# STM8.net
KiCad netlist of a schematic drawn in Altium Designer
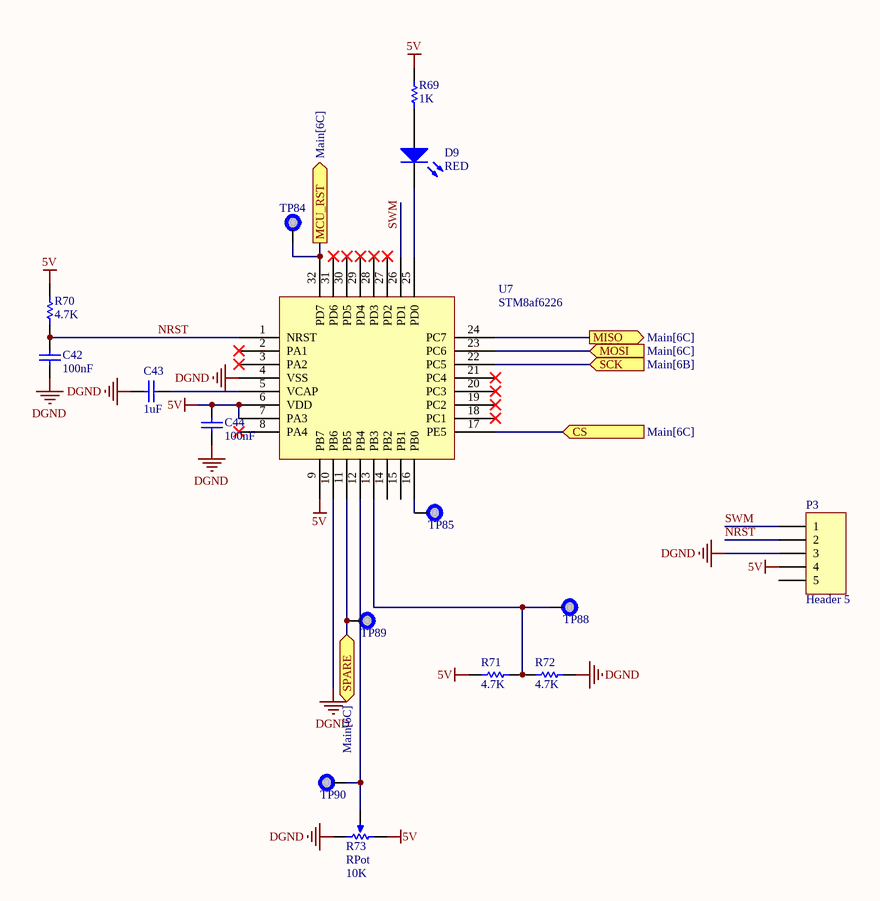
[diagram p0: STM8.SchDoc]

(export (version "E")
  (design (tool "Eeschema 10.0.6"))
  (components
    (comp (ref "C42")
      (value "100nF")
      (footprint "0603c")
      (description "LOW ESR")
      (fields (field (name "PUBLISHER") "Altium Limited"))
      (libsource (lib "Miscellaneous Devices") (part "Cap"))
    )
    (comp (ref "C43")
      (value "1uF")
      (footprint "0805c")
      (description "LOW ESR")
      (fields (field (name "PUBLISHER") "Altium Limited"))
      (libsource (lib "Miscellaneous Devices") (part "Cap"))
    )
    (comp (ref "C44")
      (value "100nF")
      (footprint "0603c")
      (description "LOW ESR")
      (fields (field (name "PUBLISHER") "Altium Limited"))
      (libsource (lib "Miscellaneous Devices") (part "Cap"))
    )
    (comp (ref "D9")
      (value "RED")
      (footprint "0805LED")
      (fields (field (name "PUBLISHER") "Altium Limited"))
      (libsource (lib "Miscellaneous Devices") (part "LED0"))
    )
    (comp (ref "P3")
      (value "Header 5")
      (footprint "HDR1X5")
      (description "Header, 5-Pin")
      (fields (field (name "PUBLISHER") "Altium Limited"))
      (libsource (lib "Miscellaneous Connectors") (part "Header 5"))
    )
    (comp (ref "R69")
      (value "1K")
      (footprint "0805")
      (description "Resistor")
      (fields (field (name "PUBLISHER") "Altium Limited"))
      (libsource (lib "Miscellaneous Devices") (part "Res1"))
    )
    (comp (ref "R70")
      (value "4.7K")
      (footprint "0805")
      (description "Resistor")
      (fields (field (name "PUBLISHER") "Altium Limited"))
      (libsource (lib "Miscellaneous Devices") (part "Res1"))
    )
    (comp (ref "R71")
      (value "4.7K")
      (footprint "0805")
      (description "Resistor")
      (fields (field (name "PUBLISHER") "Altium Limited"))
      (libsource (lib "Miscellaneous Devices") (part "Res1"))
    )
    (comp (ref "R72")
      (value "4.7K")
      (footprint "0805")
      (description "Resistor")
      (fields (field (name "PUBLISHER") "Altium Limited"))
      (libsource (lib "Miscellaneous Devices") (part "Res1"))
    )
    (comp (ref "R73")
      (value "RPot")
      (footprint "POT-MULTITURN")
      (description "MultiTurn")
      (fields (field (name "ALTIUM_VALUE") "10K") (field (name "PUBLISHER") "Altium Limited"))
      (libsource (lib "Miscellaneous Devices") (part "RPot"))
    )
    (comp (ref "TP84") (value "TestPoint") (footprint "TP") (libsource (lib "SchlibV0.1") (part "TestPoint")))
    (comp (ref "TP85") (value "TestPoint") (footprint "TP") (libsource (lib "SchlibV0.1") (part "TestPoint")))
    (comp (ref "TP88") (value "TestPoint") (footprint "TP") (libsource (lib "SchlibV0.1") (part "TestPoint")))
    (comp (ref "TP89") (value "TestPoint") (footprint "TP") (libsource (lib "SchlibV0.1") (part "TestPoint")))
    (comp (ref "TP90") (value "TestPoint") (footprint "TP") (libsource (lib "SchlibV0.1") (part "TestPoint")))
    (comp (ref "U7")
      (value "STM8af6226")
      (footprint "LQFP-32")
      (libsource (lib "SchlibV0.1") (part "STM8af6226"))
    )
  )
  (nets
    (net (code "1") (name "/CS") (class "Default")
      (node (ref "U7") (pin "17") (pinfunction "PE5_17") (pintype "passive"))
    )
    (net (code "2") (name "/MCU_RST") (class "Default")
      (node (ref "TP84") (pin "1") (pintype "passive"))
      (node (ref "U7") (pin "32") (pinfunction "PD7_32") (pintype "passive"))
    )
    (net (code "3") (name "/MISO") (class "Default")
      (node (ref "U7") (pin "24") (pinfunction "PC7_24") (pintype "passive"))
    )
    (net (code "4") (name "/MOSI") (class "Default")
      (node (ref "U7") (pin "23") (pinfunction "PC6_23") (pintype "passive"))
    )
    (net (code "5") (name "/NRST") (class "Default")
      (node (ref "C42") (pin "1") (pinfunction "1_1") (pintype "passive"))
      (node (ref "P3") (pin "2") (pinfunction "2_2") (pintype "passive"))
      (node (ref "R70") (pin "2") (pinfunction "2_2") (pintype "passive"))
      (node (ref "U7") (pin "1") (pinfunction "NRST_1") (pintype "passive"))
    )
    (net (code "6") (name "/SCK") (class "Default")
      (node (ref "U7") (pin "22") (pinfunction "PC5_22") (pintype "passive"))
    )
    (net (code "7") (name "/SPARE") (class "Default")
      (node (ref "TP89") (pin "1") (pintype "passive"))
      (node (ref "U7") (pin "11") (pinfunction "PB5_11") (pintype "passive"))
    )
    (net (code "8") (name "/SWM") (class "Default")
      (node (ref "P3") (pin "1") (pinfunction "1_1") (pintype "passive"))
      (node (ref "U7") (pin "26") (pinfunction "PD1_26") (pintype "passive"))
    )
    (net (code "9") (name "5V") (class "Default")
      (node (ref "C44") (pin "1") (pinfunction "1_1") (pintype "passive"))
      (node (ref "P3") (pin "4") (pinfunction "4_4") (pintype "passive"))
      (node (ref "R69") (pin "2") (pinfunction "2_2") (pintype "passive"))
      (node (ref "R70") (pin "1") (pinfunction "1_1") (pintype "passive"))
      (node (ref "R71") (pin "2") (pinfunction "2_2") (pintype "passive"))
      (node (ref "R73") (pin "1") (pinfunction "TOP_1") (pintype "passive"))
      (node (ref "U7") (pin "6") (pinfunction "VDD_6") (pintype "passive"))
      (node (ref "U7") (pin "7") (pinfunction "PA3_7") (pintype "passive"))
      (node (ref "U7") (pin "9") (pinfunction "PB7_9") (pintype "passive"))
    )
    (net (code "10") (name "DGND") (class "Default")
      (node (ref "C42") (pin "2") (pinfunction "2_2") (pintype "passive"))
      (node (ref "C43") (pin "2") (pinfunction "2_2") (pintype "passive"))
      (node (ref "C44") (pin "2") (pinfunction "2_2") (pintype "passive"))
      (node (ref "P3") (pin "3") (pinfunction "3_3") (pintype "passive"))
      (node (ref "R72") (pin "1") (pinfunction "1_1") (pintype "passive"))
      (node (ref "R73") (pin "3") (pinfunction "BOT_3") (pintype "passive"))
      (node (ref "U7") (pin "10") (pinfunction "PB6_10") (pintype "passive"))
      (node (ref "U7") (pin "4") (pinfunction "VSS_4") (pintype "passive"))
    )
    (net (code "11") (name "Net-(D9-A)") (class "Default")
      (node (ref "D9") (pin "1") (pinfunction "A_1") (pintype "passive"))
      (node (ref "R69") (pin "1") (pinfunction "1_1") (pintype "passive"))
    )
    (net (code "12") (name "Net-(D9-K)") (class "Default")
      (node (ref "D9") (pin "2") (pinfunction "K_2") (pintype "passive"))
      (node (ref "U7") (pin "25") (pinfunction "PD0_25") (pintype "passive"))
    )
    (net (code "13") (name "Net-(R73-TAP)") (class "Default")
      (node (ref "R73") (pin "2") (pinfunction "TAP_2") (pintype "passive"))
      (node (ref "TP90") (pin "1") (pintype "passive"))
      (node (ref "U7") (pin "12") (pinfunction "PB4_12") (pintype "passive"))
    )
    (net (code "14") (name "Net-(U7-PB0)") (class "Default")
      (node (ref "TP85") (pin "1") (pintype "passive"))
      (node (ref "U7") (pin "16") (pinfunction "PB0_16") (pintype "passive"))
    )
    (net (code "15") (name "Net-(U7-PB3)") (class "Default")
      (node (ref "R71") (pin "1") (pinfunction "1_1") (pintype "passive"))
      (node (ref "R72") (pin "2") (pinfunction "2_2") (pintype "passive"))
      (node (ref "TP88") (pin "1") (pintype "passive"))
      (node (ref "U7") (pin "13") (pinfunction "PB3_13") (pintype "passive"))
    )
    (net (code "16") (name "Net-(U7-VCAP)") (class "Default")
      (node (ref "C43") (pin "1") (pinfunction "1_1") (pintype "passive"))
      (node (ref "U7") (pin "5") (pinfunction "VCAP_5") (pintype "passive"))
    )
    (net (code "17") (name "unconnected-(P3-Pad5)") (class "Default")
      (node (ref "P3") (pin "5") (pinfunction "5_5") (pintype "passive"))
    )
    (net (code "18") (name "unconnected-(U7-PA1-Pad2)") (class "Default")
      (node (ref "U7") (pin "2") (pinfunction "PA1_2") (pintype "passive+no_connect"))
    )
    (net (code "19") (name "unconnected-(U7-PA2-Pad3)") (class "Default")
      (node (ref "U7") (pin "3") (pinfunction "PA2_3") (pintype "passive+no_connect"))
    )
    (net (code "20") (name "unconnected-(U7-PA4-Pad8)") (class "Default")
      (node (ref "U7") (pin "8") (pinfunction "PA4_8") (pintype "passive+no_connect"))
    )
    (net (code "21") (name "unconnected-(U7-PB1-Pad15)") (class "Default")
      (node (ref "U7") (pin "15") (pinfunction "PB1_15") (pintype "passive"))
    )
    (net (code "22") (name "unconnected-(U7-PB2-Pad14)") (class "Default")
      (node (ref "U7") (pin "14") (pinfunction "PB2_14") (pintype "passive"))
    )
    (net (code "23") (name "unconnected-(U7-PC1-Pad18)") (class "Default")
      (node (ref "U7") (pin "18") (pinfunction "PC1_18") (pintype "passive+no_connect"))
    )
    (net (code "24") (name "unconnected-(U7-PC2-Pad19)") (class "Default")
      (node (ref "U7") (pin "19") (pinfunction "PC2_19") (pintype "passive+no_connect"))
    )
    (net (code "25") (name "unconnected-(U7-PC3-Pad20)") (class "Default")
      (node (ref "U7") (pin "20") (pinfunction "PC3_20") (pintype "passive+no_connect"))
    )
    (net (code "26") (name "unconnected-(U7-PC4-Pad21)") (class "Default")
      (node (ref "U7") (pin "21") (pinfunction "PC4_21") (pintype "passive+no_connect"))
    )
    (net (code "27") (name "unconnected-(U7-PD2-Pad27)") (class "Default")
      (node (ref "U7") (pin "27") (pinfunction "PD2_27") (pintype "passive+no_connect"))
    )
    (net (code "28") (name "unconnected-(U7-PD3-Pad28)") (class "Default")
      (node (ref "U7") (pin "28") (pinfunction "PD3_28") (pintype "passive+no_connect"))
    )
    (net (code "29") (name "unconnected-(U7-PD4-Pad29)") (class "Default")
      (node (ref "U7") (pin "29") (pinfunction "PD4_29") (pintype "passive+no_connect"))
    )
    (net (code "30") (name "unconnected-(U7-PD5-Pad30)") (class "Default")
      (node (ref "U7") (pin "30") (pinfunction "PD5_30") (pintype "passive+no_connect"))
    )
    (net (code "31") (name "unconnected-(U7-PD6-Pad31)") (class "Default")
      (node (ref "U7") (pin "31") (pinfunction "PD6_31") (pintype "passive+no_connect"))
    )
  )
)
